# v0_4v0_4.net
KiCad netlist of a schematic drawn in EAGLE
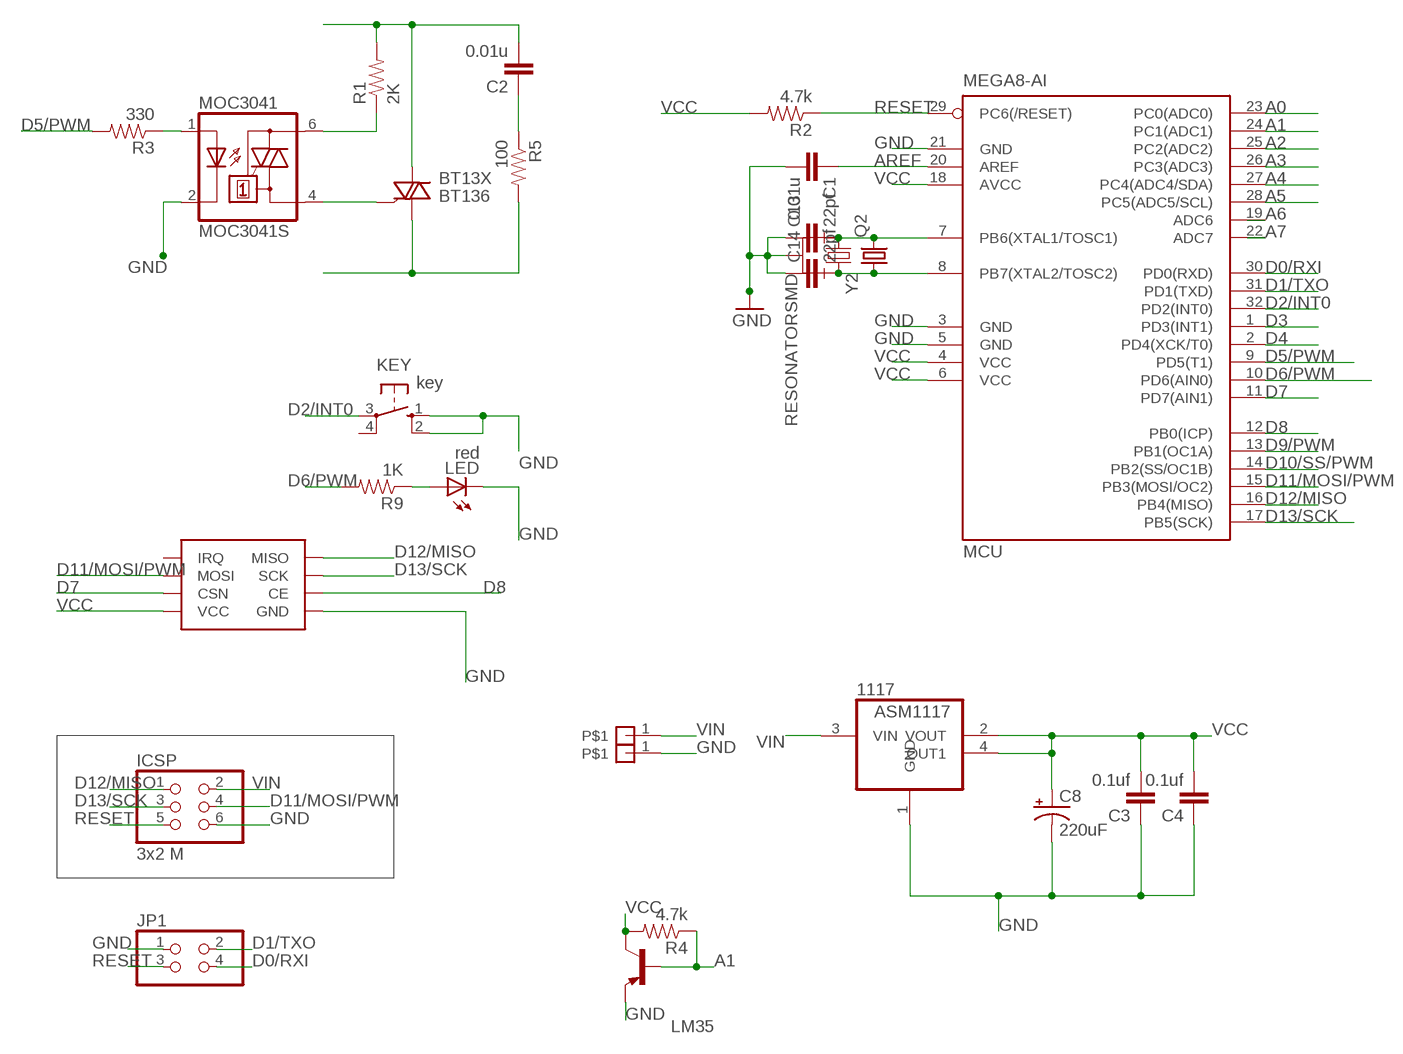
[diagram p0: schematic, sheet 1]

(export (version "E")
  (design (tool "Eeschema 10.0.6"))
  (components
    (comp (ref "1117")
      (value "ASM1117")
      (footprint "eagle-import:SOT223")
      (fields (field (name "MPN") "REG1117"))
      (libsource (lib "eagle-import") (part "ASM1117"))
    )
    (comp (ref "BT13X")
      (value "BT136")
      (footprint "eagle-import:TO252")
      (libsource (lib "eagle-import") (part "BT136"))
    )
    (comp (ref "C1")
      (value "0.01u")
      (footprint "eagle-import:0603-CAP")
      (libsource (lib "eagle-import") (part "MY2_CAP0603-CAP"))
    )
    (comp (ref "C2")
      (value "0.01u")
      (footprint "eagle-import:C050-024X044")
      (libsource (lib "eagle-import") (part "C-EU050-024X044"))
    )
    (comp (ref "C3")
      (value "0.1uf")
      (footprint "eagle-import:0603-CAP")
      (libsource (lib "eagle-import") (part "MY_CAP0603-CAP"))
    )
    (comp (ref "C4")
      (value "0.1uf")
      (footprint "eagle-import:0603-CAP")
      (libsource (lib "eagle-import") (part "MY_CAP0603-CAP"))
    )
    (comp (ref "C8")
      (value "220uF")
      (footprint "eagle-import:EIA3528")
      (libsource (lib "eagle-import") (part "CAP_POL3528"))
    )
    (comp (ref "C13")
      (value "22pf")
      (footprint "eagle-import:0603-CAP")
      (libsource (lib "eagle-import") (part "CAP0603-CAP"))
    )
    (comp (ref "C14")
      (value "22pf")
      (footprint "eagle-import:0603-CAP")
      (libsource (lib "eagle-import") (part "CAP0603-CAP"))
    )
    (comp (ref "ICSP")
      (value "3x2 M")
      (footprint "eagle-import:2X03")
      (libsource (lib "eagle-import") (part "PINHD-2X3"))
    )
    (comp (ref "JP1")
      (value "PINHD-2X2")
      (footprint "eagle-import:2X02")
      (libsource (lib "eagle-import") (part "PINHD-2X2"))
    )
    (comp (ref "KEY")
      (value "key")
      (footprint "eagle-import:B3F-10XX")
      (fields
        (field (name "MPN") "B3F-1000")
        (field (name "MPN_1") "B3F-1000")
        (field (name "OC_FARNELL") "176432")
        (field (name "OC_NEWARK") "36M3542")
      )
      (libsource (lib "eagle-import") (part "10-XX"))
    )
    (comp (ref "LED")
      (value "red")
      (footprint "eagle-import:LED3MM")
      (libsource (lib "eagle-import") (part "LED3MM"))
    )
    (comp (ref "LM35")
      (value "-PNP-TO92-E1")
      (footprint "eagle-import:TO92-E1")
      (libsource (lib "eagle-import") (part "-PNP-TO92-E1"))
    )
    (comp (ref "MCU")
      (value "MEGA8-AI")
      (footprint "eagle-import:TQFP32-08")
      (fields (field (name "MPN") "ATMEGA8-16AU"))
      (libsource (lib "eagle-import") (part "MEGA8-AI"))
    )
    (comp (ref "MOC3041")
      (value "MOC3041S")
      (footprint "eagle-import:DIL6-SMD")
      (fields
        (field (name "MF") "FAIRCHILD SEMICONDUCTOR")
        (field (name "MPN") "MOC3041S-M")
        (field (name "MF_1") "FAIRCHILD SEMICONDUCTOR")
        (field (name "MPN_1") "MOC3041S-M")
        (field (name "OC_NEWARK") "05C2885")
      )
      (libsource (lib "eagle-import") (part "MOC30S41"))
    )
    (comp (ref "Q2")
      (value "CRYSTALHC49S")
      (footprint "eagle-import:HC49_S")
      (libsource (lib "eagle-import") (part "CRYSTALHC49S"))
    )
    (comp (ref "R1")
      (value "2K")
      (footprint "eagle-import:AXIAL-0.3")
      (libsource (lib "eagle-import") (part "MY3_RESISTORPTH1"))
    )
    (comp (ref "R2")
      (value "4.7k")
      (footprint "eagle-import:0603-RES")
      (libsource (lib "eagle-import") (part "RESISTOR0603-RES"))
    )
    (comp (ref "R3")
      (value "330")
      (footprint "eagle-import:0603-RES")
      (libsource (lib "eagle-import") (part "RESISTOR0603-RES"))
    )
    (comp (ref "R4")
      (value "4.7k")
      (footprint "eagle-import:0603-RES")
      (libsource (lib "eagle-import") (part "RESISTOR0603-RES"))
    )
    (comp (ref "R5")
      (value "100")
      (footprint "eagle-import:AXIAL-0.3")
      (libsource (lib "eagle-import") (part "MY3_RESISTORPTH1"))
    )
    (comp (ref "R9")
      (value "1K")
      (footprint "eagle-import:0603-RES")
      (libsource (lib "eagle-import") (part "RESISTOR0603-RES"))
    )
    (comp (ref "U$3")
      (value "PIN1")
      (footprint "eagle-import:PIN1")
      (libsource (lib "eagle-import") (part "PIN1"))
    )
    (comp (ref "U$4")
      (value "PIN1")
      (footprint "eagle-import:PIN1")
      (libsource (lib "eagle-import") (part "PIN1"))
    )
    (comp (ref "U$6")
      (value "NRF")
      (footprint "eagle-import:NRF")
      (libsource (lib "eagle-import") (part "NRF"))
    )
    (comp (ref "Y2")
      (value "RESONATORSMD")
      (footprint "eagle-import:RESONATOR-SMD")
      (libsource (lib "eagle-import") (part "RESONATORSMD"))
    )
  )
  (nets
    (net (code "1") (name "/A0") (class "Default")
      (node (ref "MCU") (pin "23") (pinfunction "PC0(ADC0)_23") (pintype "bidirectional"))
    )
    (net (code "2") (name "/A1") (class "Default")
      (node (ref "LM35") (pin "2") (pinfunction "B_2") (pintype "passive"))
      (node (ref "MCU") (pin "24") (pinfunction "PC1(ADC1)_24") (pintype "bidirectional"))
      (node (ref "R4") (pin "1") (pinfunction "1_1") (pintype "passive"))
    )
    (net (code "3") (name "/A2") (class "Default")
      (node (ref "MCU") (pin "25") (pinfunction "PC2(ADC2)_25") (pintype "bidirectional"))
    )
    (net (code "4") (name "/A3") (class "Default")
      (node (ref "MCU") (pin "26") (pinfunction "PC3(ADC3)_26") (pintype "bidirectional"))
    )
    (net (code "5") (name "/A4") (class "Default")
      (node (ref "MCU") (pin "27") (pinfunction "PC4(ADC4/SDA)_27") (pintype "bidirectional"))
    )
    (net (code "6") (name "/A5") (class "Default")
      (node (ref "MCU") (pin "28") (pinfunction "PC5(ADC5/SCL)_28") (pintype "bidirectional"))
    )
    (net (code "7") (name "/A6") (class "Default")
      (node (ref "MCU") (pin "19") (pinfunction "ADC6_19") (pintype "bidirectional"))
    )
    (net (code "8") (name "/A7") (class "Default")
      (node (ref "MCU") (pin "22") (pinfunction "ADC7_22") (pintype "bidirectional"))
    )
    (net (code "9") (name "/AREF") (class "Default")
      (node (ref "C1") (pin "1") (pinfunction "1_1") (pintype "passive"))
      (node (ref "MCU") (pin "20") (pinfunction "AREF_20") (pintype "passive"))
    )
    (net (code "10") (name "/D0{slash}RXI") (class "Default")
      (node (ref "JP1") (pin "4") (pinfunction "4_4") (pintype "passive"))
      (node (ref "MCU") (pin "30") (pinfunction "PD0(RXD)_30") (pintype "bidirectional"))
    )
    (net (code "11") (name "/D1{slash}TXO") (class "Default")
      (node (ref "JP1") (pin "2") (pinfunction "2_2") (pintype "passive"))
      (node (ref "MCU") (pin "31") (pinfunction "PD1(TXD)_31") (pintype "bidirectional"))
    )
    (net (code "12") (name "/D2{slash}INT0") (class "Default")
      (node (ref "KEY") (pin "3") (pinfunction "P_3") (pintype "passive"))
      (node (ref "MCU") (pin "32") (pinfunction "PD2(INT0)_32") (pintype "bidirectional"))
    )
    (net (code "13") (name "/D3") (class "Default")
      (node (ref "MCU") (pin "1") (pinfunction "PD3(INT1)_1") (pintype "bidirectional"))
    )
    (net (code "14") (name "/D4") (class "Default")
      (node (ref "MCU") (pin "2") (pinfunction "PD4(XCK/T0)_2") (pintype "bidirectional"))
    )
    (net (code "15") (name "/D5{slash}PWM") (class "Default")
      (node (ref "MCU") (pin "9") (pinfunction "PD5(T1)_9") (pintype "bidirectional"))
      (node (ref "R3") (pin "2") (pinfunction "2_2") (pintype "passive"))
    )
    (net (code "16") (name "/D6{slash}PWM") (class "Default")
      (node (ref "MCU") (pin "10") (pinfunction "PD6(AIN0)_10") (pintype "bidirectional"))
      (node (ref "R9") (pin "2") (pinfunction "2_2") (pintype "passive"))
    )
    (net (code "17") (name "/D7") (class "Default")
      (node (ref "MCU") (pin "11") (pinfunction "PD7(AIN1)_11") (pintype "bidirectional"))
      (node (ref "U$6") (pin "P$4") (pinfunction "CSN_P$4") (pintype "bidirectional"))
    )
    (net (code "18") (name "/D8") (class "Default")
      (node (ref "MCU") (pin "12") (pinfunction "PB0(ICP)_12") (pintype "bidirectional"))
      (node (ref "U$6") (pin "P$3") (pinfunction "CE_P$3") (pintype "bidirectional"))
    )
    (net (code "19") (name "/D9{slash}PWM") (class "Default")
      (node (ref "MCU") (pin "13") (pinfunction "PB1(OC1A)_13") (pintype "bidirectional"))
    )
    (net (code "20") (name "/D10{slash}SS{slash}PWM") (class "Default")
      (node (ref "MCU") (pin "14") (pinfunction "PB2(SS/OC1B)_14") (pintype "bidirectional"))
    )
    (net (code "21") (name "/D11{slash}MOSI{slash}PWM") (class "Default")
      (node (ref "ICSP") (pin "4") (pinfunction "4_4") (pintype "passive"))
      (node (ref "MCU") (pin "15") (pinfunction "PB3(MOSI/OC2)_15") (pintype "bidirectional"))
      (node (ref "U$6") (pin "P$6") (pinfunction "MOSI_P$6") (pintype "bidirectional"))
    )
    (net (code "22") (name "/D12{slash}MISO") (class "Default")
      (node (ref "ICSP") (pin "1") (pinfunction "1_1") (pintype "passive"))
      (node (ref "MCU") (pin "16") (pinfunction "PB4(MISO)_16") (pintype "bidirectional"))
      (node (ref "U$6") (pin "P$7") (pinfunction "MISO_P$7") (pintype "bidirectional"))
    )
    (net (code "23") (name "/D13{slash}SCK") (class "Default")
      (node (ref "ICSP") (pin "3") (pinfunction "3_3") (pintype "passive"))
      (node (ref "MCU") (pin "17") (pinfunction "PB5(SCK)_17") (pintype "bidirectional"))
      (node (ref "U$6") (pin "P$5") (pinfunction "SCK_P$5") (pintype "bidirectional"))
    )
    (net (code "24") (name "/RESET") (class "Default")
      (node (ref "ICSP") (pin "5") (pinfunction "5_5") (pintype "passive"))
      (node (ref "JP1") (pin "3") (pinfunction "3_3") (pintype "passive"))
      (node (ref "MCU") (pin "29") (pinfunction "PC6(/RESET)_29") (pintype "bidirectional"))
      (node (ref "R2") (pin "1") (pinfunction "1_1") (pintype "passive"))
    )
    (net (code "25") (name "/VCC") (class "Default")
      (node (ref "1117") (pin "2") (pinfunction "VOUT_2") (pintype "output"))
      (node (ref "1117") (pin "4") (pinfunction "OUT1_4") (pintype "bidirectional"))
      (node (ref "C3") (pin "2") (pinfunction "2_2") (pintype "passive"))
      (node (ref "C4") (pin "2") (pinfunction "2_2") (pintype "passive"))
      (node (ref "C8") (pin "A") (pinfunction "+_A") (pintype "passive"))
      (node (ref "LM35") (pin "1") (pinfunction "C_1") (pintype "passive"))
      (node (ref "MCU") (pin "18") (pinfunction "AVCC_18") (pintype "power_in"))
      (node (ref "MCU") (pin "4") (pinfunction "VCC_4") (pintype "power_in"))
      (node (ref "MCU") (pin "6") (pinfunction "VCC_6") (pintype "power_in"))
      (node (ref "R2") (pin "2") (pinfunction "2_2") (pintype "passive"))
      (node (ref "R4") (pin "2") (pinfunction "2_2") (pintype "passive"))
      (node (ref "U$6") (pin "P$2") (pinfunction "VCC_P$2") (pintype "bidirectional"))
    )
    (net (code "26") (name "/VIN") (class "Default")
      (node (ref "1117") (pin "3") (pinfunction "VIN_3") (pintype "input"))
      (node (ref "ICSP") (pin "2") (pinfunction "2_2") (pintype "passive"))
      (node (ref "U$3") (pin "1") (pinfunction "P$1_1") (pintype "bidirectional"))
    )
    (net (code "27") (name "GND") (class "Default")
      (node (ref "1117") (pin "1") (pinfunction "GND_1") (pintype "power_in"))
      (node (ref "C1") (pin "2") (pinfunction "2_2") (pintype "passive"))
      (node (ref "C13") (pin "1") (pinfunction "1_1") (pintype "passive"))
      (node (ref "C14") (pin "1") (pinfunction "1_1") (pintype "passive"))
      (node (ref "C3") (pin "1") (pinfunction "1_1") (pintype "passive"))
      (node (ref "C4") (pin "1") (pinfunction "1_1") (pintype "passive"))
      (node (ref "C8") (pin "C") (pinfunction "-_C") (pintype "passive"))
      (node (ref "ICSP") (pin "6") (pinfunction "6_6") (pintype "passive"))
      (node (ref "JP1") (pin "1") (pinfunction "1_1") (pintype "passive"))
      (node (ref "KEY") (pin "1") (pinfunction "S_1") (pintype "passive"))
      (node (ref "KEY") (pin "2") (pinfunction "S1_2") (pintype "passive"))
      (node (ref "LED") (pin "K") (pinfunction "C_K") (pintype "passive"))
      (node (ref "LM35") (pin "3") (pinfunction "E_3") (pintype "passive"))
      (node (ref "MCU") (pin "21") (pinfunction "GND_21") (pintype "power_in"))
      (node (ref "MCU") (pin "3") (pinfunction "GND_3") (pintype "power_in"))
      (node (ref "MCU") (pin "5") (pinfunction "GND_5") (pintype "power_in"))
      (node (ref "MOC3041") (pin "2") (pinfunction "C_2") (pintype "passive"))
      (node (ref "U$4") (pin "1") (pinfunction "P$1_1") (pintype "bidirectional"))
      (node (ref "U$6") (pin "P$1") (pinfunction "GND_P$1") (pintype "bidirectional"))
      (node (ref "Y2") (pin "2") (pinfunction "2_2") (pintype "passive"))
    )
    (net (code "28") (name "Net-(BT13X-A1)") (class "Default")
      (node (ref "BT13X") (pin "1") (pinfunction "A1_1") (pintype "passive"))
      (node (ref "R5") (pin "P$2") (pinfunction "2_P$2") (pintype "passive"))
    )
    (net (code "29") (name "Net-(BT13X-A2)") (class "Default")
      (node (ref "BT13X") (pin "3") (pinfunction "A2_3") (pintype "passive"))
      (node (ref "C2") (pin "2") (pinfunction "2_2") (pintype "passive"))
      (node (ref "R1") (pin "P$2") (pinfunction "2_P$2") (pintype "passive"))
    )
    (net (code "30") (name "Net-(BT13X-G)") (class "Default")
      (node (ref "BT13X") (pin "2") (pinfunction "G_2") (pintype "passive"))
      (node (ref "MOC3041") (pin "4") (pinfunction "A1_4") (pintype "passive"))
    )
    (net (code "31") (name "Net-(LED-PadA)") (class "Default")
      (node (ref "LED") (pin "A") (pinfunction "A_A") (pintype "passive"))
      (node (ref "R9") (pin "1") (pinfunction "1_1") (pintype "passive"))
    )
    (net (code "32") (name "Net-(MCU-PB6(XTAL1{slash}TOSC1))") (class "Default")
      (node (ref "C13") (pin "2") (pinfunction "2_2") (pintype "passive"))
      (node (ref "MCU") (pin "7") (pinfunction "PB6(XTAL1/TOSC1)_7") (pintype "bidirectional"))
      (node (ref "Q2") (pin "2") (pinfunction "2_2") (pintype "passive"))
      (node (ref "Y2") (pin "1") (pinfunction "1_1") (pintype "passive"))
    )
    (net (code "33") (name "Net-(MCU-PB7(XTAL2{slash}TOSC2))") (class "Default")
      (node (ref "C14") (pin "2") (pinfunction "2_2") (pintype "passive"))
      (node (ref "MCU") (pin "8") (pinfunction "PB7(XTAL2/TOSC2)_8") (pintype "bidirectional"))
      (node (ref "Q2") (pin "1") (pinfunction "1_1") (pintype "passive"))
      (node (ref "Y2") (pin "3") (pinfunction "3_3") (pintype "passive"))
    )
    (net (code "34") (name "Net-(MOC3041-A)") (class "Default")
      (node (ref "MOC3041") (pin "1") (pinfunction "A_1") (pintype "passive"))
      (node (ref "R3") (pin "1") (pinfunction "1_1") (pintype "passive"))
    )
    (net (code "35") (name "Net-(MOC3041-A2)") (class "Default")
      (node (ref "MOC3041") (pin "6") (pinfunction "A2_6") (pintype "passive"))
      (node (ref "R1") (pin "P$1") (pinfunction "1_P$1") (pintype "passive"))
    )
    (net (code "36") (name "Net-(R5-1)") (class "Default")
      (node (ref "C2") (pin "1") (pinfunction "1_1") (pintype "passive"))
      (node (ref "R5") (pin "P$1") (pinfunction "1_P$1") (pintype "passive"))
    )
    (net (code "37") (name "unconnected-(KEY-P1-Pad4)") (class "Default")
      (node (ref "KEY") (pin "4") (pinfunction "P1_4") (pintype "passive"))
    )
    (net (code "38") (name "unconnected-(U$6-IRQ-PadP$8)") (class "Default")
      (node (ref "U$6") (pin "P$8") (pinfunction "IRQ_P$8") (pintype "bidirectional"))
    )
  )
)
